# komagoma-2.net
KiCad netlist of a schematic drawn in EAGLE
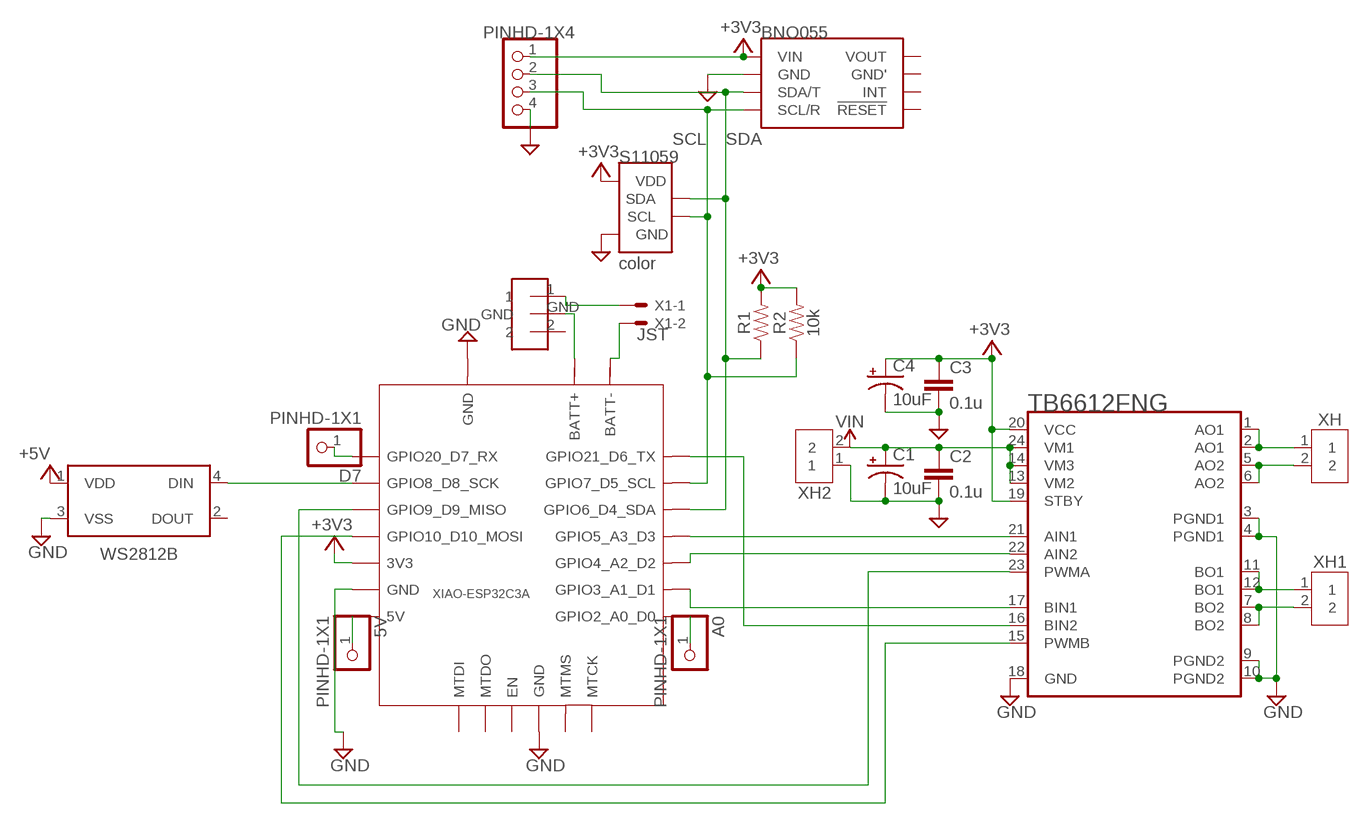
[diagram p0: schematic, sheet 1]

(export (version "E")
  (design (tool "Eeschema 10.0.6"))
  (components
    (comp (ref "5V")
      (value "PINHD-1X1")
      (footprint "eagle-import:1X01")
      (libsource (lib "eagle-import") (part "PINHD-1X1"))
    )
    (comp (ref "A0")
      (value "PINHD-1X1")
      (footprint "eagle-import:1X01")
      (libsource (lib "eagle-import") (part "PINHD-1X1"))
    )
    (comp (ref "C1")
      (value "10uF")
      (footprint "eagle-import:CPOL-RADIAL-2.5MM-5MM-KIT")
      (libsource (lib "eagle-import") (part "10UF-POLAR-RADIAL-2.5MM-KIT-25V-20%"))
    )
    (comp (ref "C2")
      (value "0.1u")
      (footprint "eagle-import:C1608")
      (libsource (lib "eagle-import") (part "C-EUC1608"))
    )
    (comp (ref "C3")
      (value "0.1u")
      (footprint "eagle-import:C1608")
      (libsource (lib "eagle-import") (part "C-EUC1608"))
    )
    (comp (ref "C4")
      (value "10uF")
      (footprint "eagle-import:CPOL-RADIAL-2.5MM-5MM-KIT")
      (libsource (lib "eagle-import") (part "10UF-POLAR-RADIAL-2.5MM-KIT-25V-20%"))
    )
    (comp (ref "CONNECTOR1")
      (value "AKIZUKI_SWITCH_SOCKETAKIZUKI_SWITCH_SOCKET")
      (footprint "eagle-import:AKIZUKI_SWITCH")
      (libsource (lib "eagle-import") (part "AKIZUKI_SWITCH_SOCKETAKIZUKI_SWITCH_SOCKET"))
    )
    (comp (ref "D1")
      (value "WS2812B")
      (footprint "eagle-import:WS2812B")
      (fields (field (name "MANUFACTURER") "Worldsemi"))
      (libsource (lib "eagle-import") (part "WS2812B"))
    )
    (comp (ref "D7")
      (value "PINHD-1X1")
      (footprint "eagle-import:1X01")
      (libsource (lib "eagle-import") (part "PINHD-1X1"))
    )
    (comp (ref "IC1")
      (value "TB6612FNGSSOP24")
      (footprint "eagle-import:SOP65P760X160-24N")
      (fields (field (name "MANUFACTURER") "Toshiba") (field (name "MPN") "TB6612FNG,C,8,EL"))
      (libsource (lib "eagle-import") (part "TB6612FNGSSOP24"))
    )
    (comp (ref "JP1")
      (value "PINHD-1X4")
      (footprint "eagle-import:1X04")
      (libsource (lib "eagle-import") (part "PINHD-1X4"))
    )
    (comp (ref "R1")
      (value "10k")
      (footprint "eagle-import:0603")
      (libsource (lib "eagle-import") (part "10KOHM-0603-1/10W-1%"))
    )
    (comp (ref "R2")
      (value "10k")
      (footprint "eagle-import:0603")
      (libsource (lib "eagle-import") (part "10KOHM-0603-1/10W-1%"))
    )
    (comp (ref "U$1")
      (value "BNO055")
      (footprint "eagle-import:BNO055")
      (libsource (lib "eagle-import") (part "BNO055"))
    )
    (comp (ref "U$2")
      (value "S11059")
      (footprint "eagle-import:S11059")
      (libsource (lib "eagle-import") (part "S11059"))
    )
    (comp (ref "U1")
      (value "XIAO-ESP32C3A")
      (footprint "eagle-import:XIAO-ESP32C3-THRUHOLE")
      (libsource (lib "eagle-import") (part "XIAO-ESP32C3A"))
    )
    (comp (ref "X1")
      (value "JST-XH-02-PIN-LONG-PAD")
      (footprint "eagle-import:JST-XH-02-PACKAGE-LONG-PAD")
      (libsource (lib "eagle-import") (part "JST-XH-02-PIN-LONG-PAD"))
    )
    (comp (ref "XH")
      (value "3A/250V")
      (footprint "eagle-import:B2B-XH-A")
      (fields (field (name "MANUFACTURER") "JST (XH CONNECTOR)") (field (name "MPN") "B2B-XH-A"))
      (libsource (lib "eagle-import") (part "B2B-XH-A"))
    )
    (comp (ref "XH1")
      (value "3A/250V")
      (footprint "eagle-import:B2B-XH-A")
      (fields (field (name "MANUFACTURER") "JST (XH CONNECTOR)") (field (name "MPN") "B2B-XH-A"))
      (libsource (lib "eagle-import") (part "B2B-XH-A"))
    )
    (comp (ref "XH2")
      (value "3A/250V")
      (footprint "eagle-import:B2B-XH-A")
      (fields (field (name "MANUFACTURER") "JST (XH CONNECTOR)") (field (name "MPN") "B2B-XH-A"))
      (libsource (lib "eagle-import") (part "B2B-XH-A"))
    )
  )
  (nets
    (net (code "1") (name "+3V3") (class "Default")
      (node (ref "C3") (pin "1") (pinfunction "1_1") (pintype "passive"))
      (node (ref "C4") (pin "1") (pinfunction "+_1") (pintype "passive"))
      (node (ref "IC1") (pin "19") (pinfunction "STBY_19") (pintype "input"))
      (node (ref "IC1") (pin "20") (pinfunction "VCC_20") (pintype "power_in"))
      (node (ref "JP1") (pin "1") (pinfunction "1_1") (pintype "passive"))
      (node (ref "R1") (pin "2") (pinfunction "2_2") (pintype "passive"))
      (node (ref "R2") (pin "2") (pinfunction "2_2") (pintype "passive"))
      (node (ref "U$1") (pin "P$1") (pinfunction "VIN_P$1") (pintype "bidirectional"))
      (node (ref "U$2") (pin "P$4") (pinfunction "VDD_P$4") (pintype "bidirectional"))
      (node (ref "U1") (pin "P$12") (pinfunction "3V3_P$12") (pintype "bidirectional"))
    )
    (net (code "2") (name "+5V") (class "Default")
      (node (ref "D1") (pin "1") (pinfunction "VDD_1") (pintype "power_in"))
    )
    (net (code "3") (name "/SCL") (class "Default")
      (node (ref "JP1") (pin "3") (pinfunction "3_3") (pintype "passive"))
      (node (ref "R2") (pin "1") (pinfunction "1_1") (pintype "passive"))
      (node (ref "U$1") (pin "P$4") (pinfunction "SCL/R_P$4") (pintype "bidirectional"))
      (node (ref "U$2") (pin "P$2") (pinfunction "SCL_P$2") (pintype "bidirectional"))
      (node (ref "U1") (pin "P$6") (pinfunction "GPIO7_D5_SCL_P$6") (pintype "bidirectional"))
    )
    (net (code "4") (name "/SDA") (class "Default")
      (node (ref "JP1") (pin "2") (pinfunction "2_2") (pintype "passive"))
      (node (ref "R1") (pin "1") (pinfunction "1_1") (pintype "passive"))
      (node (ref "U$1") (pin "P$3") (pinfunction "SDA/T_P$3") (pintype "bidirectional"))
      (node (ref "U$2") (pin "P$3") (pinfunction "SDA_P$3") (pintype "bidirectional"))
      (node (ref "U1") (pin "P$5") (pinfunction "GPIO6_D4_SDA_P$5") (pintype "bidirectional"))
    )
    (net (code "5") (name "GND") (class "Default")
      (node (ref "C1") (pin "2") (pinfunction "-_2") (pintype "passive"))
      (node (ref "C2") (pin "2") (pinfunction "2_2") (pintype "passive"))
      (node (ref "C3") (pin "2") (pinfunction "2_2") (pintype "passive"))
      (node (ref "C4") (pin "2") (pinfunction "-_2") (pintype "passive"))
      (node (ref "D1") (pin "3") (pinfunction "VSS_3") (pintype "power_in"))
      (node (ref "IC1") (pin "10") (pinfunction "PGND2_10") (pintype "power_in"))
      (node (ref "IC1") (pin "18") (pinfunction "GND_18") (pintype "power_in"))
      (node (ref "IC1") (pin "3") (pinfunction "PGND1_3") (pintype "power_in"))
      (node (ref "IC1") (pin "4") (pinfunction "PGND1_4") (pintype "power_in"))
      (node (ref "IC1") (pin "9") (pinfunction "PGND2_9") (pintype "power_in"))
      (node (ref "JP1") (pin "4") (pinfunction "4_4") (pintype "passive"))
      (node (ref "U$1") (pin "P$2") (pinfunction "GND_P$2") (pintype "bidirectional"))
      (node (ref "U$2") (pin "P$1") (pinfunction "GND_P$1") (pintype "bidirectional"))
      (node (ref "U1") (pin "18") (pinfunction "GND_18") (pintype "bidirectional"))
      (node (ref "U1") (pin "23") (pinfunction "GND_23") (pintype "bidirectional"))
      (node (ref "U1") (pin "P$13") (pinfunction "GND_P$13") (pintype "bidirectional"))
      (node (ref "XH2") (pin "1") (pinfunction "1_1") (pintype "bidirectional"))
    )
    (net (code "6") (name "Net-(C1-+)") (class "Default")
      (node (ref "C1") (pin "1") (pinfunction "+_1") (pintype "passive"))
      (node (ref "C2") (pin "1") (pinfunction "1_1") (pintype "passive"))
      (node (ref "IC1") (pin "13") (pinfunction "VM2_13") (pintype "power_in"))
      (node (ref "IC1") (pin "14") (pinfunction "VM3_14") (pintype "power_in"))
      (node (ref "IC1") (pin "24") (pinfunction "VM1_24") (pintype "power_in"))
      (node (ref "XH2") (pin "2") (pinfunction "2_2") (pintype "bidirectional"))
    )
    (net (code "7") (name "Net-(D1-DIN)") (class "Default")
      (node (ref "D1") (pin "4") (pinfunction "DIN_4") (pintype "input"))
      (node (ref "U1") (pin "P$9") (pinfunction "GPIO8_D8_SCK_P$9") (pintype "bidirectional"))
    )
    (net (code "8") (name "Net-(IC1-AIN1)") (class "Default")
      (node (ref "IC1") (pin "21") (pinfunction "AIN1_21") (pintype "input"))
      (node (ref "U1") (pin "P$4") (pinfunction "GPIO5_A3_D3_P$4") (pintype "bidirectional"))
    )
    (net (code "9") (name "Net-(IC1-AIN2)") (class "Default")
      (node (ref "IC1") (pin "22") (pinfunction "AIN2_22") (pintype "input"))
      (node (ref "U1") (pin "P$3") (pinfunction "GPIO4_A2_D2_P$3") (pintype "bidirectional"))
    )
    (net (code "10") (name "Net-(IC1-AO1-Pad1)") (class "Default")
      (node (ref "IC1") (pin "1") (pinfunction "AO1_1") (pintype "output"))
      (node (ref "IC1") (pin "2") (pinfunction "AO1_2") (pintype "output"))
      (node (ref "XH") (pin "1") (pinfunction "1_1") (pintype "bidirectional"))
    )
    (net (code "11") (name "Net-(IC1-AO2-Pad5)") (class "Default")
      (node (ref "IC1") (pin "5") (pinfunction "AO2_5") (pintype "output"))
      (node (ref "IC1") (pin "6") (pinfunction "AO2_6") (pintype "output"))
      (node (ref "XH") (pin "2") (pinfunction "2_2") (pintype "bidirectional"))
    )
    (net (code "12") (name "Net-(IC1-BIN1)") (class "Default")
      (node (ref "IC1") (pin "17") (pinfunction "BIN1_17") (pintype "input"))
      (node (ref "U1") (pin "P$2") (pinfunction "GPIO3_A1_D1_P$2") (pintype "bidirectional"))
    )
    (net (code "13") (name "Net-(IC1-BIN2)") (class "Default")
      (node (ref "IC1") (pin "16") (pinfunction "BIN2_16") (pintype "input"))
      (node (ref "U1") (pin "P$7") (pinfunction "GPIO21_D6_TX_P$7") (pintype "bidirectional"))
    )
    (net (code "14") (name "Net-(IC1-BO1-Pad11)") (class "Default")
      (node (ref "IC1") (pin "11") (pinfunction "BO1_11") (pintype "output"))
      (node (ref "IC1") (pin "12") (pinfunction "BO1_12") (pintype "output"))
      (node (ref "XH1") (pin "1") (pinfunction "1_1") (pintype "bidirectional"))
    )
    (net (code "15") (name "Net-(IC1-BO2-Pad7)") (class "Default")
      (node (ref "IC1") (pin "7") (pinfunction "BO2_7") (pintype "output"))
      (node (ref "IC1") (pin "8") (pinfunction "BO2_8") (pintype "output"))
      (node (ref "XH1") (pin "2") (pinfunction "2_2") (pintype "bidirectional"))
    )
    (net (code "16") (name "Net-(IC1-PWMA)") (class "Default")
      (node (ref "IC1") (pin "23") (pinfunction "PWMA_23") (pintype "input"))
      (node (ref "U1") (pin "P$10") (pinfunction "GPIO9_D9_MISO_P$10") (pintype "bidirectional"))
    )
    (net (code "17") (name "Net-(IC1-PWMB)") (class "Default")
      (node (ref "IC1") (pin "15") (pinfunction "PWMB_15") (pintype "input"))
      (node (ref "U1") (pin "P$11") (pinfunction "GPIO10_D10_MOSI_P$11") (pintype "bidirectional"))
    )
    (net (code "18") (name "Net-(U1-5V)") (class "Default")
      (node (ref "5V") (pin "1") (pinfunction "1_1") (pintype "passive"))
      (node (ref "U1") (pin "P$14") (pinfunction "5V_P$14") (pintype "bidirectional"))
    )
    (net (code "19") (name "Net-(U1-BATT+)") (class "Default")
      (node (ref "CONNECTOR1") (pin "GND") (pinfunction "GND_GND") (pintype "bidirectional"))
      (node (ref "U1") (pin "22") (pinfunction "BATT+_22") (pintype "bidirectional"))
    )
    (net (code "20") (name "Net-(U1-BATT-)") (class "Default")
      (node (ref "U1") (pin "21") (pinfunction "BATT-_21") (pintype "bidirectional"))
      (node (ref "X1") (pin "2") (pinfunction "S_2") (pintype "passive"))
    )
    (net (code "21") (name "Net-(U1-GPIO2_A0_D0)") (class "Default")
      (node (ref "A0") (pin "1") (pinfunction "1_1") (pintype "passive"))
      (node (ref "U1") (pin "P$1") (pinfunction "GPIO2_A0_D0_P$1") (pintype "bidirectional"))
    )
    (net (code "22") (name "Net-(U1-GPIO20_D7_RX)") (class "Default")
      (node (ref "D7") (pin "1") (pinfunction "1_1") (pintype "passive"))
      (node (ref "U1") (pin "P$8") (pinfunction "GPIO20_D7_RX_P$8") (pintype "bidirectional"))
    )
    (net (code "23") (name "Net-(X1A-S)") (class "Default")
      (node (ref "CONNECTOR1") (pin "1") (pinfunction "1_1") (pintype "bidirectional"))
      (node (ref "X1") (pin "1") (pinfunction "S_1") (pintype "passive"))
    )
    (net (code "25") (name "unconnected-(CONNECTOR1-Pad2)") (class "Default")
      (node (ref "CONNECTOR1") (pin "2") (pinfunction "2_2") (pintype "bidirectional"))
    )
    (net (code "26") (name "unconnected-(D1-DOUT-Pad2)") (class "Default")
      (node (ref "D1") (pin "2") (pinfunction "DOUT_2") (pintype "output"))
    )
    (net (code "27") (name "unconnected-(U$1-GND'-PadP$7)") (class "Default")
      (node (ref "U$1") (pin "P$7") (pinfunction "GND'_P$7") (pintype "bidirectional"))
    )
    (net (code "28") (name "unconnected-(U$1-INT-PadP$6)") (class "Default")
      (node (ref "U$1") (pin "P$6") (pinfunction "INT_P$6") (pintype "bidirectional"))
    )
    (net (code "29") (name "unconnected-(U$1-VOUT-PadP$8)") (class "Default")
      (node (ref "U$1") (pin "P$8") (pinfunction "VOUT_P$8") (pintype "bidirectional"))
    )
    (net (code "30") (name "unconnected-(U$1-~{RESET}-PadP$5)") (class "Default")
      (node (ref "U$1") (pin "P$5") (pinfunction "~{RESET}_P$5") (pintype "bidirectional"))
    )
    (net (code "31") (name "unconnected-(U1-EN-Pad17)") (class "Default")
      (node (ref "U1") (pin "17") (pinfunction "EN_17") (pintype "bidirectional"))
    )
    (net (code "32") (name "unconnected-(U1-MTCK-Pad20)") (class "Default")
      (node (ref "U1") (pin "20") (pinfunction "MTCK_20") (pintype "bidirectional"))
    )
    (net (code "33") (name "unconnected-(U1-MTDI-Pad15)") (class "Default")
      (node (ref "U1") (pin "15") (pinfunction "MTDI_15") (pintype "bidirectional"))
    )
    (net (code "34") (name "unconnected-(U1-MTDO-Pad16)") (class "Default")
      (node (ref "U1") (pin "16") (pinfunction "MTDO_16") (pintype "bidirectional"))
    )
    (net (code "35") (name "unconnected-(U1-MTMS-Pad19)") (class "Default")
      (node (ref "U1") (pin "19") (pinfunction "MTMS_19") (pintype "bidirectional"))
    )
  )
)
